# DFPLAYER.net
KiCad netlist of a schematic drawn in EasyEDA
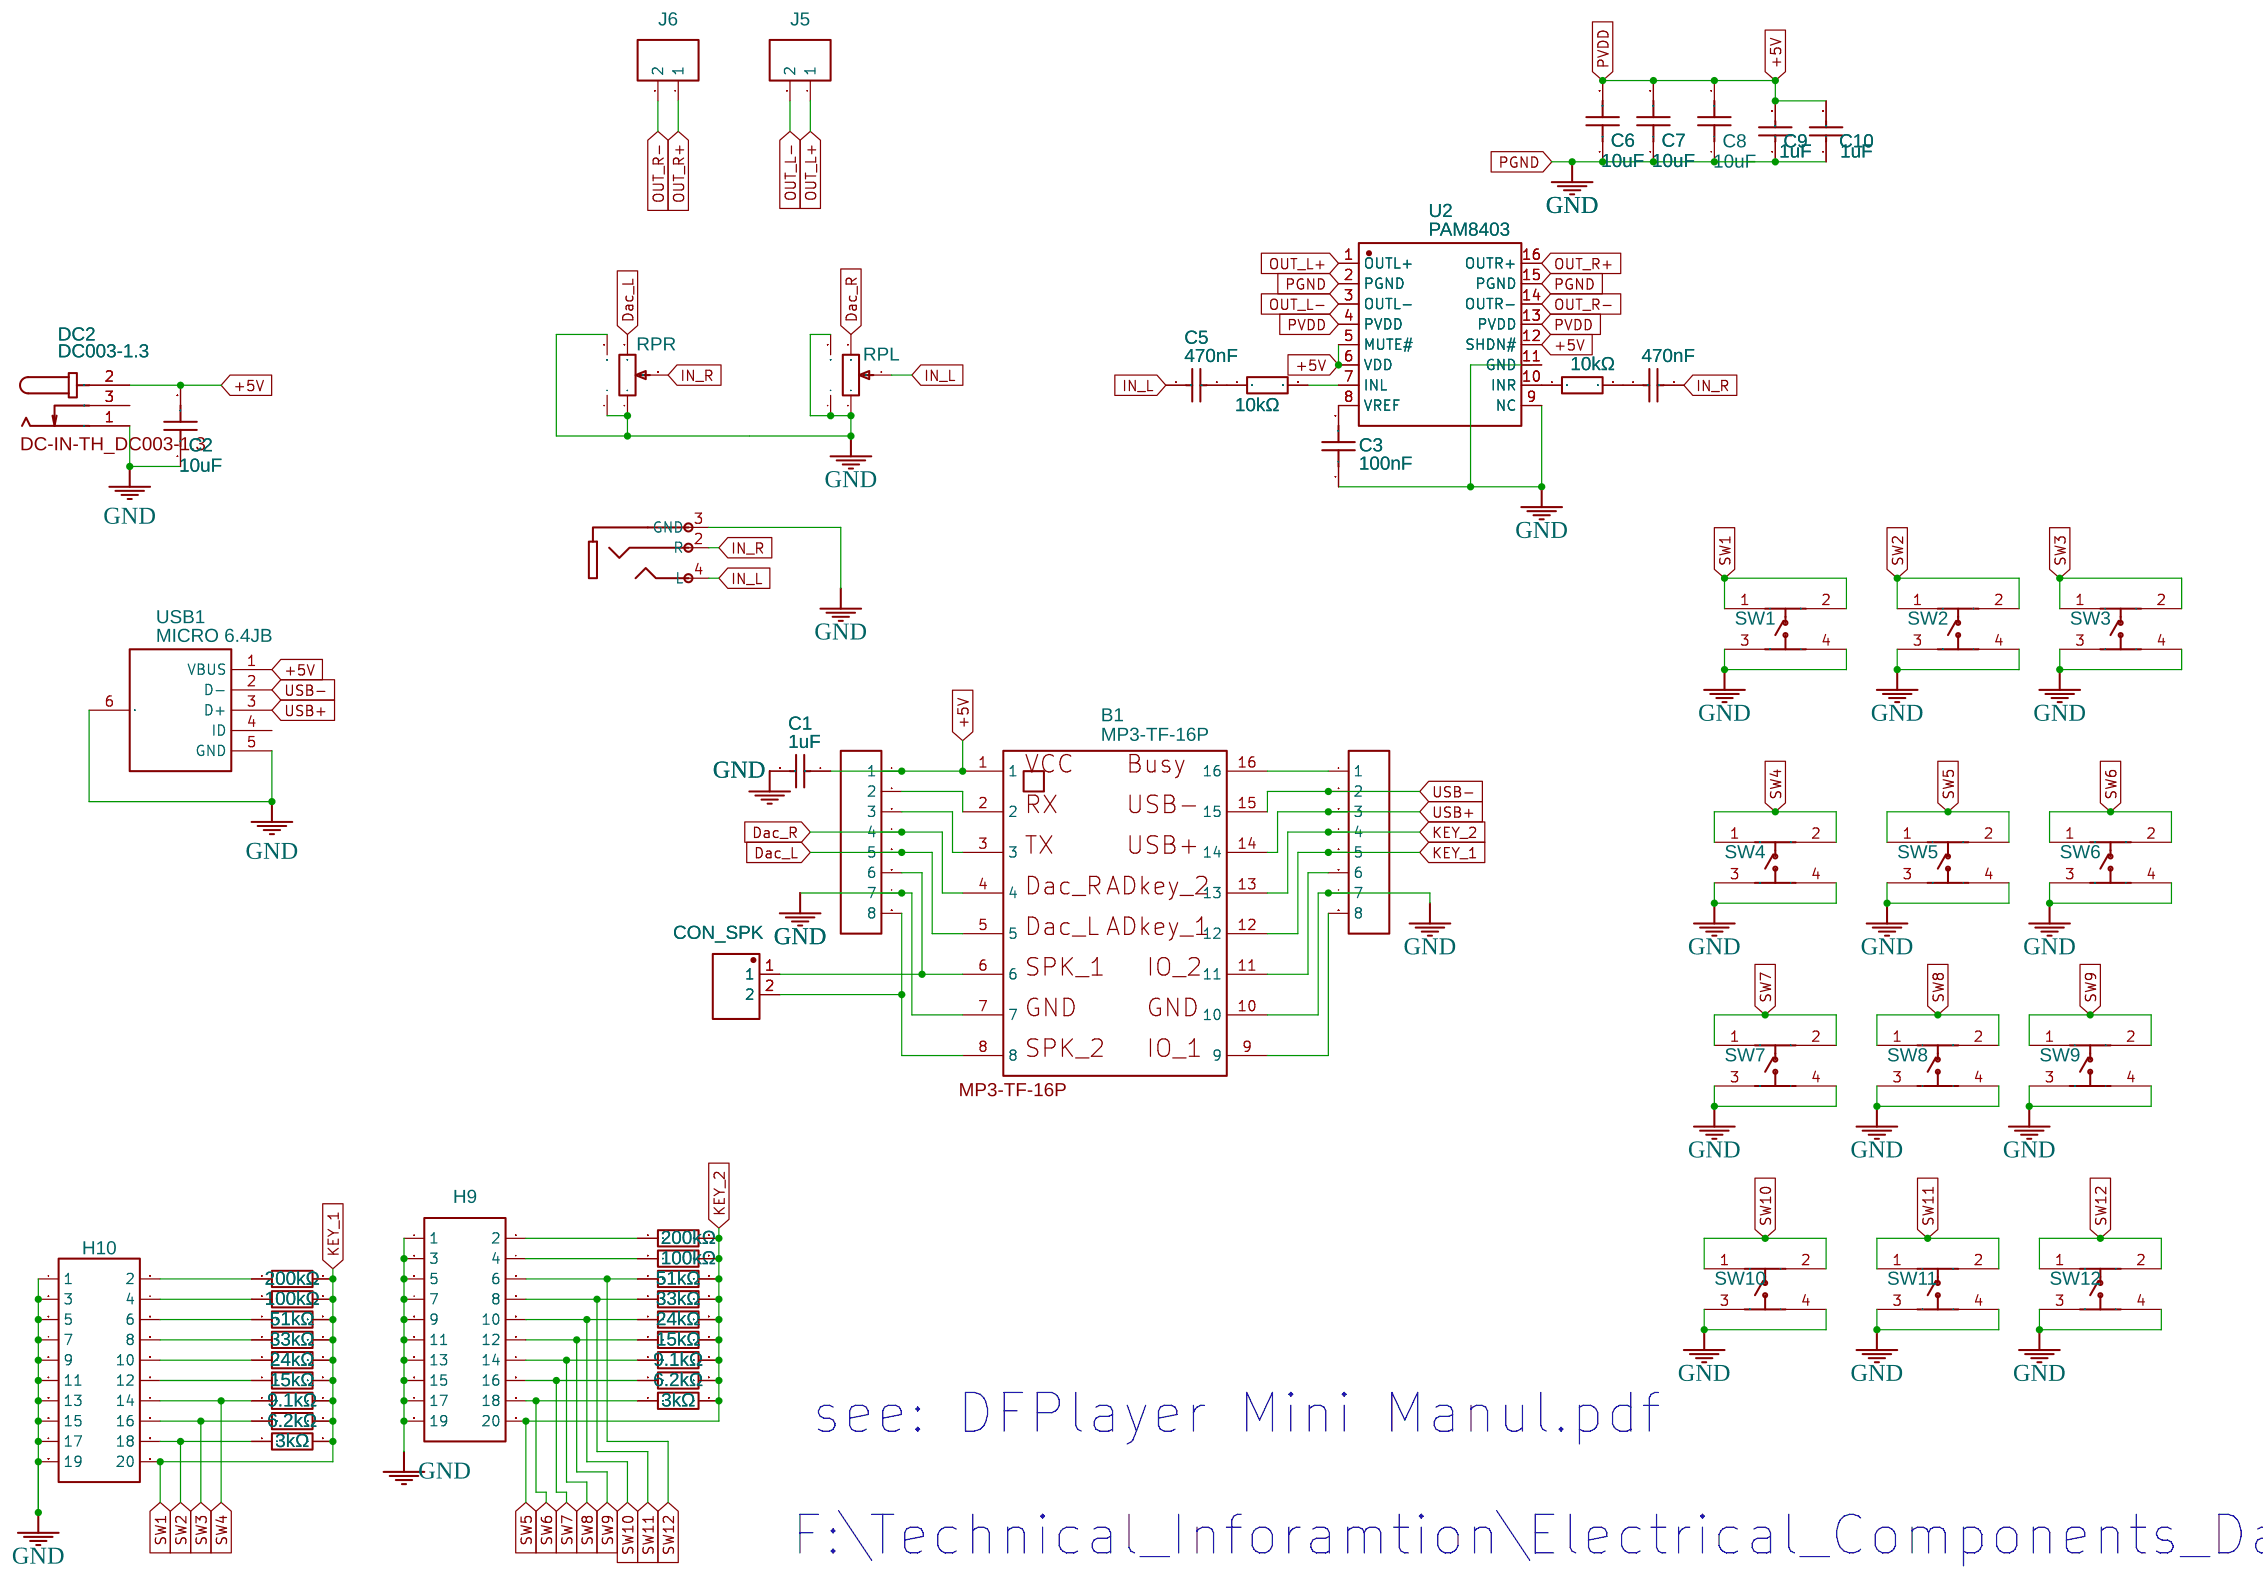
[diagram p0: schematic sheet]

(export (version "E")
  (design (tool "Eeschema 10.0.6"))
  (components
    (comp (ref "B1") (value "MP3-TF-16P") (libsource (lib "") (part "MP3-TF-16P")))
    (comp (ref "C1")
      (value "1uF")
      (fields
        (field (name "Manufacturer Part") "CL10A105KB8NNNC")
        (field (name "Manufacturer") "SAMSUNG(三星)")
      )
      (libsource (lib "") (part "CL10A105KB8NNNC_1"))
    )
    (comp (ref "C2")
      (value "10uF")
      (fields
        (field (name "Manufacturer Part") "CL10A106MA8NRNC")
        (field (name "Manufacturer") "SAMSUNG(三星)")
      )
      (libsource (lib "") (part "CL10A106MA8NRNC"))
    )
    (comp (ref "C3")
      (value "100nF")
      (fields
        (field (name "Manufacturer Part") "CC0603KRX7R9BB104")
        (field (name "Manufacturer") "YAGEO(国巨)")
      )
      (libsource (lib "") (part "CC0603KRX7R9BB104"))
    )
    (comp (ref "C4")
      (value "470nF")
      (fields
        (field (name "Manufacturer Part") "CL10B474KA8NNNC")
        (field (name "Manufacturer") "SAMSUNG(三星)")
      )
      (libsource (lib "") (part "CL10B474KA8NNNC"))
    )
    (comp (ref "C5")
      (value "470nF")
      (fields
        (field (name "Manufacturer Part") "CL10B474KA8NNNC")
        (field (name "Manufacturer") "SAMSUNG(三星)")
      )
      (libsource (lib "") (part "CL10B474KA8NNNC"))
    )
    (comp (ref "C6")
      (value "10uF")
      (fields
        (field (name "Manufacturer Part") "CL10A106MA8NRNC")
        (field (name "Manufacturer") "SAMSUNG(三星)")
      )
      (libsource (lib "") (part "CL10A106MA8NRNC"))
    )
    (comp (ref "C7")
      (value "10uF")
      (fields
        (field (name "Manufacturer Part") "CL10A106MA8NRNC")
        (field (name "Manufacturer") "SAMSUNG(三星)")
      )
      (libsource (lib "") (part "CL10A106MA8NRNC"))
    )
    (comp (ref "C8")
      (value "10uF")
      (fields
        (field (name "Manufacturer Part") "CL10A106MA8NRNC")
        (field (name "Manufacturer") "SAMSUNG(三星)")
      )
      (libsource (lib "") (part "CL10A106MA8NRNC"))
    )
    (comp (ref "C9")
      (value "1uF")
      (fields
        (field (name "Manufacturer Part") "CL10A105KB8NNNC")
        (field (name "Manufacturer") "SAMSUNG(三星)")
      )
      (libsource (lib "") (part "CL10A105KB8NNNC"))
    )
    (comp (ref "C10")
      (value "1uF")
      (fields
        (field (name "Manufacturer Part") "CL10A105KB8NNNC")
        (field (name "Manufacturer") "SAMSUNG(三星)")
      )
      (libsource (lib "") (part "CL10A105KB8NNNC"))
    )
    (comp (ref "CON_SPK")
      (value "640456-2")
      (fields (field (name "BOM_Supplier Part") "C86502"))
      (libsource (lib "") (part "640456-2"))
    )
    (comp (ref "DC2")
      (value "DC003-1.3")
      (fields (field (name "Manufacturer") "SHOU HAN(首韩)"))
      (libsource (lib "") (part "DC003-1.3"))
    )
    (comp (ref "H9")
      (value "HDR-F-2.54_2x10")
      (fields (field (name "BOM_Supplier Part") "C30867"))
      (libsource (lib "") (part "HDR-F-2.54_2x10"))
    )
    (comp (ref "H10")
      (value "HDR-F-2.54_2x10")
      (fields (field (name "BOM_Supplier Part") "C30867"))
      (libsource (lib "") (part "HDR-F-2.54_2x10"))
    )
    (comp (ref "J1")
      (value "HDR-M-2.54_1x8")
      (fields (field (name "BOM_Supplier Part") "C190820"))
      (libsource (lib "") (part "HDR-M-2.54_1x8_1"))
    )
    (comp (ref "J2")
      (value "HDR-M-2.54_1x8")
      (fields (field (name "BOM_Supplier Part") "C190820"))
      (libsource (lib "") (part "HDR-M-2.54_1x8"))
    )
    (comp (ref "J3")
      (value "Black headphone jack")
      (fields (field (name "Manufacturer Part") "320B直插") (field (name "Manufacturer") "BOOMELE(博穆精密)"))
      (libsource (lib "") (part "Black headphone jack"))
    )
    (comp (ref "J5")
      (value "HDR-M-2.54_1x2")
      (fields (field (name "BOM_Supplier Part") "C124375"))
      (libsource (lib "") (part "HDR-M-2.54_1x2"))
    )
    (comp (ref "J6")
      (value "HDR-M-2.54_1x2")
      (fields (field (name "BOM_Supplier Part") "C124375"))
      (libsource (lib "") (part "HDR-M-2.54_1x2"))
    )
    (comp (ref "R2")
      (value "3kΩ")
      (fields
        (field (name "Manufacturer Part") "0603WAF3001T5E")
        (field (name "Manufacturer") "UNI-ROYAL(厚声)")
      )
      (libsource (lib "") (part "0603WAF3001T5E"))
    )
    (comp (ref "R3")
      (value "6.2kΩ")
      (fields
        (field (name "Manufacturer Part") "0603WAF6201T5E")
        (field (name "Manufacturer") "UNI-ROYAL(厚声)")
      )
      (libsource (lib "") (part "0603WAF6201T5E"))
    )
    (comp (ref "R4")
      (value "9.1kΩ")
      (fields
        (field (name "Manufacturer Part") "0603WAF9101T5E")
        (field (name "Manufacturer") "UNI-ROYAL(厚声)")
      )
      (libsource (lib "") (part "0603WAF9101T5E"))
    )
    (comp (ref "R5")
      (value "15kΩ")
      (fields
        (field (name "Manufacturer Part") "0603WAF1502T5E")
        (field (name "Manufacturer") "UNI-ROYAL(厚声)")
      )
      (libsource (lib "") (part "0603WAF1502T5E"))
    )
    (comp (ref "R6")
      (value "24kΩ")
      (fields
        (field (name "Manufacturer Part") "0603WAF2402T5E")
        (field (name "Manufacturer") "UNI-ROYAL(厚声)")
      )
      (libsource (lib "") (part "0603WAF2402T5E"))
    )
    (comp (ref "R7")
      (value "33kΩ")
      (fields
        (field (name "Manufacturer Part") "0603WAF3302T5E")
        (field (name "Manufacturer") "UNI-ROYAL(厚声)")
      )
      (libsource (lib "") (part "0603WAF3302T5E"))
    )
    (comp (ref "R8")
      (value "51kΩ")
      (fields
        (field (name "Manufacturer Part") "0603WAF5102T5E")
        (field (name "Manufacturer") "UNI-ROYAL(厚声)")
      )
      (libsource (lib "") (part "0603WAF5102T5E"))
    )
    (comp (ref "R9")
      (value "100kΩ")
      (fields
        (field (name "Manufacturer Part") "0603WAF1003T5E")
        (field (name "Manufacturer") "UNI-ROYAL(厚声)")
      )
      (libsource (lib "") (part "0603WAF1003T5E"))
    )
    (comp (ref "R10")
      (value "200kΩ")
      (fields
        (field (name "Manufacturer Part") "0603WAF2003T5E")
        (field (name "Manufacturer") "UNI-ROYAL(厚声)")
      )
      (libsource (lib "") (part "0603WAF2003T5E"))
    )
    (comp (ref "R11")
      (value "10kΩ")
      (fields
        (field (name "Manufacturer Part") "0603WAF1002T5E")
        (field (name "Manufacturer") "UNI-ROYAL(厚声)")
      )
      (libsource (lib "") (part "0603WAF1002T5E"))
    )
    (comp (ref "R12")
      (value "3kΩ")
      (fields
        (field (name "Manufacturer Part") "0603WAF3001T5E")
        (field (name "Manufacturer") "UNI-ROYAL(厚声)")
      )
      (libsource (lib "") (part "0603WAF3001T5E"))
    )
    (comp (ref "R13")
      (value "6.2kΩ")
      (fields
        (field (name "Manufacturer Part") "0603WAF6201T5E")
        (field (name "Manufacturer") "UNI-ROYAL(厚声)")
      )
      (libsource (lib "") (part "0603WAF6201T5E"))
    )
    (comp (ref "R14")
      (value "9.1kΩ")
      (fields
        (field (name "Manufacturer Part") "0603WAF9101T5E")
        (field (name "Manufacturer") "UNI-ROYAL(厚声)")
      )
      (libsource (lib "") (part "0603WAF9101T5E"))
    )
    (comp (ref "R15")
      (value "15kΩ")
      (fields
        (field (name "Manufacturer Part") "0603WAF1502T5E")
        (field (name "Manufacturer") "UNI-ROYAL(厚声)")
      )
      (libsource (lib "") (part "0603WAF1502T5E"))
    )
    (comp (ref "R16")
      (value "24kΩ")
      (fields
        (field (name "Manufacturer Part") "0603WAF2402T5E")
        (field (name "Manufacturer") "UNI-ROYAL(厚声)")
      )
      (libsource (lib "") (part "0603WAF2402T5E"))
    )
    (comp (ref "R17")
      (value "33kΩ")
      (fields
        (field (name "Manufacturer Part") "0603WAF3302T5E")
        (field (name "Manufacturer") "UNI-ROYAL(厚声)")
      )
      (libsource (lib "") (part "0603WAF3302T5E"))
    )
    (comp (ref "R18")
      (value "51kΩ")
      (fields
        (field (name "Manufacturer Part") "0603WAF5102T5E")
        (field (name "Manufacturer") "UNI-ROYAL(厚声)")
      )
      (libsource (lib "") (part "0603WAF5102T5E"))
    )
    (comp (ref "R19")
      (value "100kΩ")
      (fields
        (field (name "Manufacturer Part") "0603WAF1003T5E")
        (field (name "Manufacturer") "UNI-ROYAL(厚声)")
      )
      (libsource (lib "") (part "0603WAF1003T5E"))
    )
    (comp (ref "R20")
      (value "200kΩ")
      (fields
        (field (name "Manufacturer Part") "0603WAF2003T5E")
        (field (name "Manufacturer") "UNI-ROYAL(厚声)")
      )
      (libsource (lib "") (part "0603WAF2003T5E"))
    )
    (comp (ref "R21")
      (value "10kΩ")
      (fields
        (field (name "Manufacturer Part") "0603WAF1002T5E")
        (field (name "Manufacturer") "UNI-ROYAL(厚声)")
      )
      (libsource (lib "") (part "0603WAF1002T5E"))
    )
    (comp (ref "RPL")
      (value "长柄旋转电位器")
      (fields (field (name "BOM_Supplier Part") "C2874842"))
      (libsource (lib "") (part "长柄旋转电位器_1"))
    )
    (comp (ref "RPR")
      (value "长柄旋转电位器")
      (fields (field (name "BOM_Supplier Part") "C2874842"))
      (libsource (lib "") (part "长柄旋转电位器"))
    )
    (comp (ref "SW1")
      (value "6.0*6.0*6.0")
      (fields (field (name "Manufacturer") "BOOMELE(博穆精密)"))
      (libsource (lib "") (part "6.0*6.0*6.0"))
    )
    (comp (ref "SW2")
      (value "6.0*6.0*6.0")
      (fields (field (name "Manufacturer") "BOOMELE(博穆精密)"))
      (libsource (lib "") (part "6.0*6.0*6.0"))
    )
    (comp (ref "SW3")
      (value "6.0*6.0*6.0")
      (fields (field (name "Manufacturer") "BOOMELE(博穆精密)"))
      (libsource (lib "") (part "6.0*6.0*6.0"))
    )
    (comp (ref "SW4")
      (value "6.0*6.0*6.0")
      (fields (field (name "Manufacturer") "BOOMELE(博穆精密)"))
      (libsource (lib "") (part "6.0*6.0*6.0"))
    )
    (comp (ref "SW5")
      (value "6.0*6.0*6.0")
      (fields (field (name "Manufacturer") "BOOMELE(博穆精密)"))
      (libsource (lib "") (part "6.0*6.0*6.0"))
    )
    (comp (ref "SW6")
      (value "6.0*6.0*6.0")
      (fields (field (name "Manufacturer") "BOOMELE(博穆精密)"))
      (libsource (lib "") (part "6.0*6.0*6.0"))
    )
    (comp (ref "SW7")
      (value "6.0*6.0*6.0")
      (fields (field (name "Manufacturer") "BOOMELE(博穆精密)"))
      (libsource (lib "") (part "6.0*6.0*6.0"))
    )
    (comp (ref "SW8")
      (value "6.0*6.0*6.0")
      (fields (field (name "Manufacturer") "BOOMELE(博穆精密)"))
      (libsource (lib "") (part "6.0*6.0*6.0"))
    )
    (comp (ref "SW9")
      (value "6.0*6.0*6.0")
      (fields (field (name "Manufacturer") "BOOMELE(博穆精密)"))
      (libsource (lib "") (part "6.0*6.0*6.0"))
    )
    (comp (ref "SW10")
      (value "6.0*6.0*6.0")
      (fields (field (name "Manufacturer") "BOOMELE(博穆精密)"))
      (libsource (lib "") (part "6.0*6.0*6.0"))
    )
    (comp (ref "SW11")
      (value "6.0*6.0*6.0")
      (fields (field (name "Manufacturer") "BOOMELE(博穆精密)"))
      (libsource (lib "") (part "6.0*6.0*6.0"))
    )
    (comp (ref "SW12")
      (value "6.0*6.0*6.0")
      (fields (field (name "Manufacturer") "BOOMELE(博穆精密)"))
      (libsource (lib "") (part "6.0*6.0*6.0"))
    )
    (comp (ref "U2")
      (value "PAM8403")
      (fields (field (name "Manufacturer") "Slkor(萨科微)"))
      (libsource (lib "") (part "PAM8403"))
    )
    (comp (ref "USB1")
      (value "MICRO 6.4JB")
      (fields (field (name "Manufacturer") "SHOU HAN(首韩)"))
      (libsource (lib "") (part "MICRO 6.4JB"))
    )
  )
  (nets
    (net (code "1") (name "+5V") (class "Default")
      (node (ref "B1") (pin "1") (pinfunction "1_1") (pintype "unspecified"))
      (node (ref "C1") (pin "1") (pinfunction "1_1") (pintype "input"))
      (node (ref "C10") (pin "2") (pinfunction "2_2") (pintype "input"))
      (node (ref "C2") (pin "2") (pinfunction "2_2") (pintype "unspecified"))
      (node (ref "C6") (pin "2") (pinfunction "2_2") (pintype "unspecified"))
      (node (ref "C7") (pin "2") (pinfunction "2_2") (pintype "unspecified"))
      (node (ref "C8") (pin "2") (pinfunction "2_2") (pintype "unspecified"))
      (node (ref "C9") (pin "2") (pinfunction "2_2") (pintype "input"))
      (node (ref "DC2") (pin "2") (pinfunction "2_2") (pintype "unspecified"))
      (node (ref "J1") (pin "1") (pinfunction "1_1") (pintype "unspecified"))
      (node (ref "U2") (pin "12") (pinfunction "SHDN#_12") (pintype "unspecified"))
      (node (ref "U2") (pin "13") (pinfunction "PVDD_13") (pintype "unspecified"))
      (node (ref "U2") (pin "4") (pinfunction "PVDD_4") (pintype "unspecified"))
      (node (ref "U2") (pin "5") (pinfunction "MUTE#_5") (pintype "unspecified"))
      (node (ref "U2") (pin "6") (pinfunction "VDD_6") (pintype "unspecified"))
      (node (ref "USB1") (pin "1") (pinfunction "VBUS_1") (pintype "input"))
    )
    (net (code "2") (name "Dac_L") (class "Default")
      (node (ref "B1") (pin "5") (pinfunction "5_5") (pintype "unspecified"))
      (node (ref "J1") (pin "5") (pinfunction "5_5") (pintype "unspecified"))
      (node (ref "RPR") (pin "3") (pinfunction "3_3") (pintype "input"))
    )
    (net (code "3") (name "Dac_R") (class "Default")
      (node (ref "B1") (pin "4") (pinfunction "4_4") (pintype "unspecified"))
      (node (ref "J1") (pin "4") (pinfunction "4_4") (pintype "unspecified"))
      (node (ref "RPL") (pin "3") (pinfunction "3_3") (pintype "input"))
    )
    (net (code "4") (name "IN_L") (class "Default")
      (node (ref "C5") (pin "1") (pinfunction "1_1") (pintype "input"))
      (node (ref "J3") (pin "4") (pinfunction "L_4") (pintype "input"))
      (node (ref "RPL") (pin "2") (pinfunction "2_2") (pintype "input"))
    )
    (net (code "5") (name "IN_R") (class "Default")
      (node (ref "C4") (pin "2") (pinfunction "2_2") (pintype "input"))
      (node (ref "J3") (pin "2") (pinfunction "R_2") (pintype "input"))
      (node (ref "RPR") (pin "2") (pinfunction "2_2") (pintype "input"))
    )
    (net (code "6") (name "KEY_1") (class "Default")
      (node (ref "B1") (pin "12") (pinfunction "12_12") (pintype "unspecified"))
      (node (ref "H10") (pin "20") (pinfunction "20_20") (pintype "input"))
      (node (ref "J2") (pin "5") (pinfunction "5_5") (pintype "unspecified"))
      (node (ref "R10") (pin "2") (pinfunction "2_2") (pintype "input"))
      (node (ref "R2") (pin "2") (pinfunction "2_2") (pintype "input"))
      (node (ref "R3") (pin "2") (pinfunction "2_2") (pintype "input"))
      (node (ref "R4") (pin "2") (pinfunction "2_2") (pintype "input"))
      (node (ref "R5") (pin "2") (pinfunction "2_2") (pintype "input"))
      (node (ref "R6") (pin "2") (pinfunction "2_2") (pintype "input"))
      (node (ref "R7") (pin "2") (pinfunction "2_2") (pintype "input"))
      (node (ref "R8") (pin "2") (pinfunction "2_2") (pintype "input"))
      (node (ref "R9") (pin "2") (pinfunction "2_2") (pintype "input"))
      (node (ref "SW1") (pin "1") (pinfunction "1_1") (pintype "unspecified"))
      (node (ref "SW1") (pin "2") (pinfunction "2_2") (pintype "unspecified"))
    )
    (net (code "7") (name "KEY_2") (class "Default")
      (node (ref "B1") (pin "13") (pinfunction "13_13") (pintype "unspecified"))
      (node (ref "H9") (pin "20") (pinfunction "20_20") (pintype "input"))
      (node (ref "J2") (pin "4") (pinfunction "4_4") (pintype "unspecified"))
      (node (ref "R12") (pin "2") (pinfunction "2_2") (pintype "input"))
      (node (ref "R13") (pin "2") (pinfunction "2_2") (pintype "input"))
      (node (ref "R14") (pin "2") (pinfunction "2_2") (pintype "input"))
      (node (ref "R15") (pin "2") (pinfunction "2_2") (pintype "input"))
      (node (ref "R16") (pin "2") (pinfunction "2_2") (pintype "input"))
      (node (ref "R17") (pin "2") (pinfunction "2_2") (pintype "input"))
      (node (ref "R18") (pin "2") (pinfunction "2_2") (pintype "input"))
      (node (ref "R19") (pin "2") (pinfunction "2_2") (pintype "input"))
      (node (ref "R20") (pin "2") (pinfunction "2_2") (pintype "input"))
      (node (ref "SW5") (pin "1") (pinfunction "1_1") (pintype "unspecified"))
      (node (ref "SW5") (pin "2") (pinfunction "2_2") (pintype "unspecified"))
    )
    (net (code "8") (name "Net-(B1-Pad2)") (class "Default")
      (node (ref "B1") (pin "2") (pinfunction "2_2") (pintype "unspecified"))
      (node (ref "J1") (pin "2") (pinfunction "2_2") (pintype "unspecified"))
    )
    (net (code "9") (name "Net-(B1-Pad3)") (class "Default")
      (node (ref "B1") (pin "3") (pinfunction "3_3") (pintype "unspecified"))
      (node (ref "J1") (pin "3") (pinfunction "3_3") (pintype "unspecified"))
    )
    (net (code "10") (name "Net-(B1-Pad6)") (class "Default")
      (node (ref "B1") (pin "6") (pinfunction "6_6") (pintype "unspecified"))
      (node (ref "CON_SPK") (pin "1") (pinfunction "1_1") (pintype "unspecified"))
      (node (ref "J1") (pin "6") (pinfunction "6_6") (pintype "unspecified"))
    )
    (net (code "11") (name "Net-(B1-Pad8)") (class "Default")
      (node (ref "B1") (pin "8") (pinfunction "8_8") (pintype "unspecified"))
      (node (ref "CON_SPK") (pin "2") (pinfunction "2_2") (pintype "unspecified"))
      (node (ref "J1") (pin "8") (pinfunction "8_8") (pintype "unspecified"))
    )
    (net (code "12") (name "Net-(B1-Pad9)") (class "Default")
      (node (ref "B1") (pin "9") (pinfunction "9_9") (pintype "unspecified"))
      (node (ref "J2") (pin "8") (pinfunction "8_8") (pintype "unspecified"))
    )
    (net (code "13") (name "Net-(B1-Pad11)") (class "Default")
      (node (ref "B1") (pin "11") (pinfunction "11_11") (pintype "unspecified"))
      (node (ref "J2") (pin "6") (pinfunction "6_6") (pintype "unspecified"))
    )
    (net (code "14") (name "Net-(B1-Pad16)") (class "Default")
      (node (ref "B1") (pin "16") (pinfunction "16_16") (pintype "unspecified"))
      (node (ref "J2") (pin "1") (pinfunction "1_1") (pintype "unspecified"))
    )
    (net (code "15") (name "Net-(C4-Pad1)") (class "Default")
      (node (ref "C4") (pin "1") (pinfunction "1_1") (pintype "input"))
      (node (ref "R21") (pin "2") (pinfunction "2_2") (pintype "input"))
    )
    (net (code "16") (name "Net-(C5-Pad2)") (class "Default")
      (node (ref "C5") (pin "2") (pinfunction "2_2") (pintype "input"))
      (node (ref "R11") (pin "1") (pinfunction "1_1") (pintype "input"))
    )
    (net (code "17") (name "Net-(H9-Pad2)") (class "Default")
      (node (ref "H9") (pin "2") (pinfunction "2_2") (pintype "input"))
      (node (ref "R20") (pin "1") (pinfunction "1_1") (pintype "input"))
    )
    (net (code "18") (name "Net-(H9-Pad4)") (class "Default")
      (node (ref "H9") (pin "4") (pinfunction "4_4") (pintype "input"))
      (node (ref "R19") (pin "1") (pinfunction "1_1") (pintype "input"))
    )
    (net (code "19") (name "Net-(H10-Pad2)") (class "Default")
      (node (ref "H10") (pin "2") (pinfunction "2_2") (pintype "input"))
      (node (ref "R10") (pin "1") (pinfunction "1_1") (pintype "input"))
    )
    (net (code "20") (name "Net-(H10-Pad4)") (class "Default")
      (node (ref "H10") (pin "4") (pinfunction "4_4") (pintype "input"))
      (node (ref "R9") (pin "1") (pinfunction "1_1") (pintype "input"))
    )
    (net (code "21") (name "Net-(H10-Pad6)") (class "Default")
      (node (ref "H10") (pin "6") (pinfunction "6_6") (pintype "input"))
      (node (ref "R8") (pin "1") (pinfunction "1_1") (pintype "input"))
    )
    (net (code "22") (name "Net-(H10-Pad8)") (class "Default")
      (node (ref "H10") (pin "8") (pinfunction "8_8") (pintype "input"))
      (node (ref "R7") (pin "1") (pinfunction "1_1") (pintype "input"))
    )
    (net (code "23") (name "Net-(H10-Pad10)") (class "Default")
      (node (ref "H10") (pin "10") (pinfunction "10_10") (pintype "input"))
      (node (ref "R6") (pin "1") (pinfunction "1_1") (pintype "input"))
    )
    (net (code "24") (name "Net-(H10-Pad12)") (class "Default")
      (node (ref "H10") (pin "12") (pinfunction "12_12") (pintype "input"))
      (node (ref "R5") (pin "1") (pinfunction "1_1") (pintype "input"))
    )
    (net (code "25") (name "Net-(U2-INL)") (class "Default")
      (node (ref "R11") (pin "2") (pinfunction "2_2") (pintype "input"))
      (node (ref "U2") (pin "7") (pinfunction "INL_7") (pintype "unspecified"))
    )
    (net (code "26") (name "Net-(U2-INR)") (class "Default")
      (node (ref "R21") (pin "1") (pinfunction "1_1") (pintype "input"))
      (node (ref "U2") (pin "10") (pinfunction "INR_10") (pintype "unspecified"))
    )
    (net (code "27") (name "Net-(U2-VREF)") (class "Default")
      (node (ref "C3") (pin "2") (pinfunction "2_2") (pintype "unspecified"))
      (node (ref "U2") (pin "8") (pinfunction "VREF_8") (pintype "unspecified"))
    )
    (net (code "28") (name "OUT_L+") (class "Default")
      (node (ref "J5") (pin "1") (pinfunction "1_1") (pintype "unspecified"))
      (node (ref "U2") (pin "1") (pinfunction "OUTL+_1") (pintype "unspecified"))
    )
    (net (code "29") (name "OUT_L-") (class "Default")
      (node (ref "J5") (pin "2") (pinfunction "2_2") (pintype "unspecified"))
      (node (ref "U2") (pin "3") (pinfunction "OUTL-_3") (pintype "unspecified"))
    )
    (net (code "30") (name "OUT_R+") (class "Default")
      (node (ref "J6") (pin "1") (pinfunction "1_1") (pintype "unspecified"))
      (node (ref "U2") (pin "16") (pinfunction "OUTR+_16") (pintype "unspecified"))
    )
    (net (code "31") (name "OUT_R-") (class "Default")
      (node (ref "J6") (pin "2") (pinfunction "2_2") (pintype "unspecified"))
      (node (ref "U2") (pin "14") (pinfunction "OUTR-_14") (pintype "unspecified"))
    )
    (net (code "32") (name "PGND") (class "Default")
      (node (ref "B1") (pin "10") (pinfunction "10_10") (pintype "unspecified"))
      (node (ref "B1") (pin "7") (pinfunction "7_7") (pintype "unspecified"))
      (node (ref "C1") (pin "2") (pinfunction "2_2") (pintype "input"))
      (node (ref "C10") (pin "1") (pinfunction "1_1") (pintype "input"))
      (node (ref "C2") (pin "1") (pinfunction "1_1") (pintype "unspecified"))
      (node (ref "C3") (pin "1") (pinfunction "1_1") (pintype "unspecified"))
      (node (ref "C6") (pin "1") (pinfunction "1_1") (pintype "unspecified"))
      (node (ref "C7") (pin "1") (pinfunction "1_1") (pintype "unspecified"))
      (node (ref "C8") (pin "1") (pinfunction "1_1") (pintype "unspecified"))
      (node (ref "C9") (pin "1") (pinfunction "1_1") (pintype "input"))
      (node (ref "DC2") (pin "1") (pinfunction "1_1") (pintype "unspecified"))
      (node (ref "H10") (pin "1") (pinfunction "1_1") (pintype "input"))
      (node (ref "H10") (pin "11") (pinfunction "11_11") (pintype "input"))
      (node (ref "H10") (pin "13") (pinfunction "13_13") (pintype "input"))
      (node (ref "H10") (pin "15") (pinfunction "15_15") (pintype "input"))
      (node (ref "H10") (pin "17") (pinfunction "17_17") (pintype "input"))
      (node (ref "H10") (pin "19") (pinfunction "19_19") (pintype "input"))
      (node (ref "H10") (pin "3") (pinfunction "3_3") (pintype "input"))
      (node (ref "H10") (pin "5") (pinfunction "5_5") (pintype "input"))
      (node (ref "H10") (pin "7") (pinfunction "7_7") (pintype "input"))
      (node (ref "H10") (pin "9") (pinfunction "9_9") (pintype "input"))
      (node (ref "H9") (pin "1") (pinfunction "1_1") (pintype "input"))
      (node (ref "H9") (pin "11") (pinfunction "11_11") (pintype "input"))
      (node (ref "H9") (pin "13") (pinfunction "13_13") (pintype "input"))
      (node (ref "H9") (pin "15") (pinfunction "15_15") (pintype "input"))
      (node (ref "H9") (pin "17") (pinfunction "17_17") (pintype "input"))
      (node (ref "H9") (pin "19") (pinfunction "19_19") (pintype "input"))
      (node (ref "H9") (pin "3") (pinfunction "3_3") (pintype "input"))
      (node (ref "H9") (pin "5") (pinfunction "5_5") (pintype "input"))
      (node (ref "H9") (pin "7") (pinfunction "7_7") (pintype "input"))
      (node (ref "H9") (pin "9") (pinfunction "9_9") (pintype "input"))
      (node (ref "J1") (pin "7") (pinfunction "7_7") (pintype "unspecified"))
      (node (ref "J2") (pin "7") (pinfunction "7_7") (pintype "unspecified"))
      (node (ref "J3") (pin "3") (pinfunction "GND_3") (pintype "input"))
      (node (ref "RPL") (pin "1") (pinfunction "1_1") (pintype "input"))
      (node (ref "RPL") (pin "4") (pinfunction "4_4") (pintype "input"))
      (node (ref "RPL") (pin "5") (pinfunction "5_5") (pintype "input"))
      (node (ref "RPR") (pin "1") (pinfunction "1_1") (pintype "input"))
      (node (ref "RPR") (pin "4") (pinfunction "4_4") (pintype "input"))
      (node (ref "RPR") (pin "5") (pinfunction "5_5") (pintype "input"))
      (node (ref "SW1") (pin "3") (pinfunction "3_3") (pintype "unspecified"))
      (node (ref "SW1") (pin "4") (pinfunction "4_4") (pintype "unspecified"))
      (node (ref "SW10") (pin "3") (pinfunction "3_3") (pintype "unspecified"))
      (node (ref "SW10") (pin "4") (pinfunction "4_4") (pintype "unspecified"))
      (node (ref "SW11") (pin "3") (pinfunction "3_3") (pintype "unspecified"))
      (node (ref "SW11") (pin "4") (pinfunction "4_4") (pintype "unspecified"))
      (node (ref "SW12") (pin "3") (pinfunction "3_3") (pintype "unspecified"))
      (node (ref "SW12") (pin "4") (pinfunction "4_4") (pintype "unspecified"))
      (node (ref "SW2") (pin "3") (pinfunction "3_3") (pintype "unspecified"))
      (node (ref "SW2") (pin "4") (pinfunction "4_4") (pintype "unspecified"))
      (node (ref "SW3") (pin "3") (pinfunction "3_3") (pintype "unspecified"))
      (node (ref "SW3") (pin "4") (pinfunction "4_4") (pintype "unspecified"))
      (node (ref "SW4") (pin "3") (pinfunction "3_3") (pintype "unspecified"))
      (node (ref "SW4") (pin "4") (pinfunction "4_4") (pintype "unspecified"))
      (node (ref "SW5") (pin "3") (pinfunction "3_3") (pintype "unspecified"))
      (node (ref "SW5") (pin "4") (pinfunction "4_4") (pintype "unspecified"))
      (node (ref "SW6") (pin "3") (pinfunction "3_3") (pintype "unspecified"))
      (node (ref "SW6") (pin "4") (pinfunction "4_4") (pintype "unspecified"))
      (node (ref "SW7") (pin "3") (pinfunction "3_3") (pintype "unspecified"))
      (node (ref "SW7") (pin "4") (pinfunction "4_4") (pintype "unspecified"))
      (node (ref "SW8") (pin "3") (pinfunction "3_3") (pintype "unspecified"))
      (node (ref "SW8") (pin "4") (pinfunction "4_4") (pintype "unspecified"))
      (node (ref "SW9") (pin "3") (pinfunction "3_3") (pintype "unspecified"))
      (node (ref "SW9") (pin "4") (pinfunction "4_4") (pintype "unspecified"))
      (node (ref "U2") (pin "15") (pinfunction "PGND_15") (pintype "unspecified"))
      (node (ref "U2") (pin "2") (pinfunction "PGND_2") (pintype "unspecified"))
      (node (ref "U2") (pin "9") (pinfunction "NC_9") (pintype "unspecified"))
      (node (ref "USB1") (pin "5") (pinfunction "GND_5") (pintype "input"))
      (node (ref "USB1") (pin "6") (pinfunction "EH_6") (pintype "input"))
    )
    (net (code "33") (name "SW2") (class "Default")
      (node (ref "H10") (pin "18") (pinfunction "18_18") (pintype "input"))
      (node (ref "R2") (pin "1") (pinfunction "1_1") (pintype "input"))
      (node (ref "SW2") (pin "1") (pinfunction "1_1") (pintype "unspecified"))
      (node (ref "SW2") (pin "2") (pinfunction "2_2") (pintype "unspecified"))
    )
    (net (code "34") (name "SW3") (class "Default")
      (node (ref "H10") (pin "16") (pinfunction "16_16") (pintype "input"))
      (node (ref "R3") (pin "1") (pinfunction "1_1") (pintype "input"))
      (node (ref "SW3") (pin "1") (pinfunction "1_1") (pintype "unspecified"))
      (node (ref "SW3") (pin "2") (pinfunction "2_2") (pintype "unspecified"))
    )
    (net (code "35") (name "SW4") (class "Default")
      (node (ref "H10") (pin "14") (pinfunction "14_14") (pintype "input"))
      (node (ref "R4") (pin "1") (pinfunction "1_1") (pintype "input"))
      (node (ref "SW4") (pin "1") (pinfunction "1_1") (pintype "unspecified"))
      (node (ref "SW4") (pin "2") (pinfunction "2_2") (pintype "unspecified"))
    )
    (net (code "36") (name "SW6") (class "Default")
      (node (ref "H9") (pin "18") (pinfunction "18_18") (pintype "input"))
      (node (ref "R12") (pin "1") (pinfunction "1_1") (pintype "input"))
      (node (ref "SW6") (pin "1") (pinfunction "1_1") (pintype "unspecified"))
      (node (ref "SW6") (pin "2") (pinfunction "2_2") (pintype "unspecified"))
    )
    (net (code "37") (name "SW7") (class "Default")
      (node (ref "H9") (pin "16") (pinfunction "16_16") (pintype "input"))
      (node (ref "R13") (pin "1") (pinfunction "1_1") (pintype "input"))
      (node (ref "SW7") (pin "1") (pinfunction "1_1") (pintype "unspecified"))
      (node (ref "SW7") (pin "2") (pinfunction "2_2") (pintype "unspecified"))
    )
    (net (code "38") (name "SW8") (class "Default")
      (node (ref "H9") (pin "14") (pinfunction "14_14") (pintype "input"))
      (node (ref "R14") (pin "1") (pinfunction "1_1") (pintype "input"))
      (node (ref "SW8") (pin "1") (pinfunction "1_1") (pintype "unspecified"))
      (node (ref "SW8") (pin "2") (pinfunction "2_2") (pintype "unspecified"))
    )
    (net (code "39") (name "SW9") (class "Default")
      (node (ref "H9") (pin "12") (pinfunction "12_12") (pintype "input"))
      (node (ref "R15") (pin "1") (pinfunction "1_1") (pintype "input"))
      (node (ref "SW9") (pin "1") (pinfunction "1_1") (pintype "unspecified"))
      (node (ref "SW9") (pin "2") (pinfunction "2_2") (pintype "unspecified"))
    )
    (net (code "40") (name "SW10") (class "Default")
      (node (ref "H9") (pin "10") (pinfunction "10_10") (pintype "input"))
      (node (ref "R16") (pin "1") (pinfunction "1_1") (pintype "input"))
      (node (ref "SW10") (pin "1") (pinfunction "1_1") (pintype "unspecified"))
      (node (ref "SW10") (pin "2") (pinfunction "2_2") (pintype "unspecified"))
    )
    (net (code "41") (name "SW11") (class "Default")
      (node (ref "H9") (pin "8") (pinfunction "8_8") (pintype "input"))
      (node (ref "R17") (pin "1") (pinfunction "1_1") (pintype "input"))
      (node (ref "SW11") (pin "1") (pinfunction "1_1") (pintype "unspecified"))
      (node (ref "SW11") (pin "2") (pinfunction "2_2") (pintype "unspecified"))
    )
    (net (code "42") (name "SW12") (class "Default")
      (node (ref "H9") (pin "6") (pinfunction "6_6") (pintype "input"))
      (node (ref "R18") (pin "1") (pinfunction "1_1") (pintype "input"))
      (node (ref "SW12") (pin "1") (pinfunction "1_1") (pintype "unspecified"))
      (node (ref "SW12") (pin "2") (pinfunction "2_2") (pintype "unspecified"))
    )
    (net (code "43") (name "USB+") (class "Default")
      (node (ref "B1") (pin "14") (pinfunction "14_14") (pintype "unspecified"))
      (node (ref "J2") (pin "3") (pinfunction "3_3") (pintype "unspecified"))
      (node (ref "USB1") (pin "3") (pinfunction "D+_3") (pintype "input"))
    )
    (net (code "44") (name "USB-") (class "Default")
      (node (ref "B1") (pin "15") (pinfunction "15_15") (pintype "unspecified"))
      (node (ref "J2") (pin "2") (pinfunction "2_2") (pintype "unspecified"))
      (node (ref "USB1") (pin "2") (pinfunction "D-_2") (pintype "input"))
    )
    (net (code "45") (name "unconnected-(DC2-Pad3)") (class "Default")
      (node (ref "DC2") (pin "3") (pinfunction "3_3") (pintype "unspecified"))
    )
    (net (code "46") (name "unconnected-(U2-GND-Pad11)") (class "Default")
      (node (ref "U2") (pin "11") (pinfunction "GND_11") (pintype "unspecified"))
    )
    (net (code "47") (name "unconnected-(USB1-ID-Pad4)") (class "Default")
      (node (ref "USB1") (pin "4") (pinfunction "ID_4") (pintype "input"))
    )
  )
)
